# lid.net
KiCad netlist of a schematic drawn in EAGLE
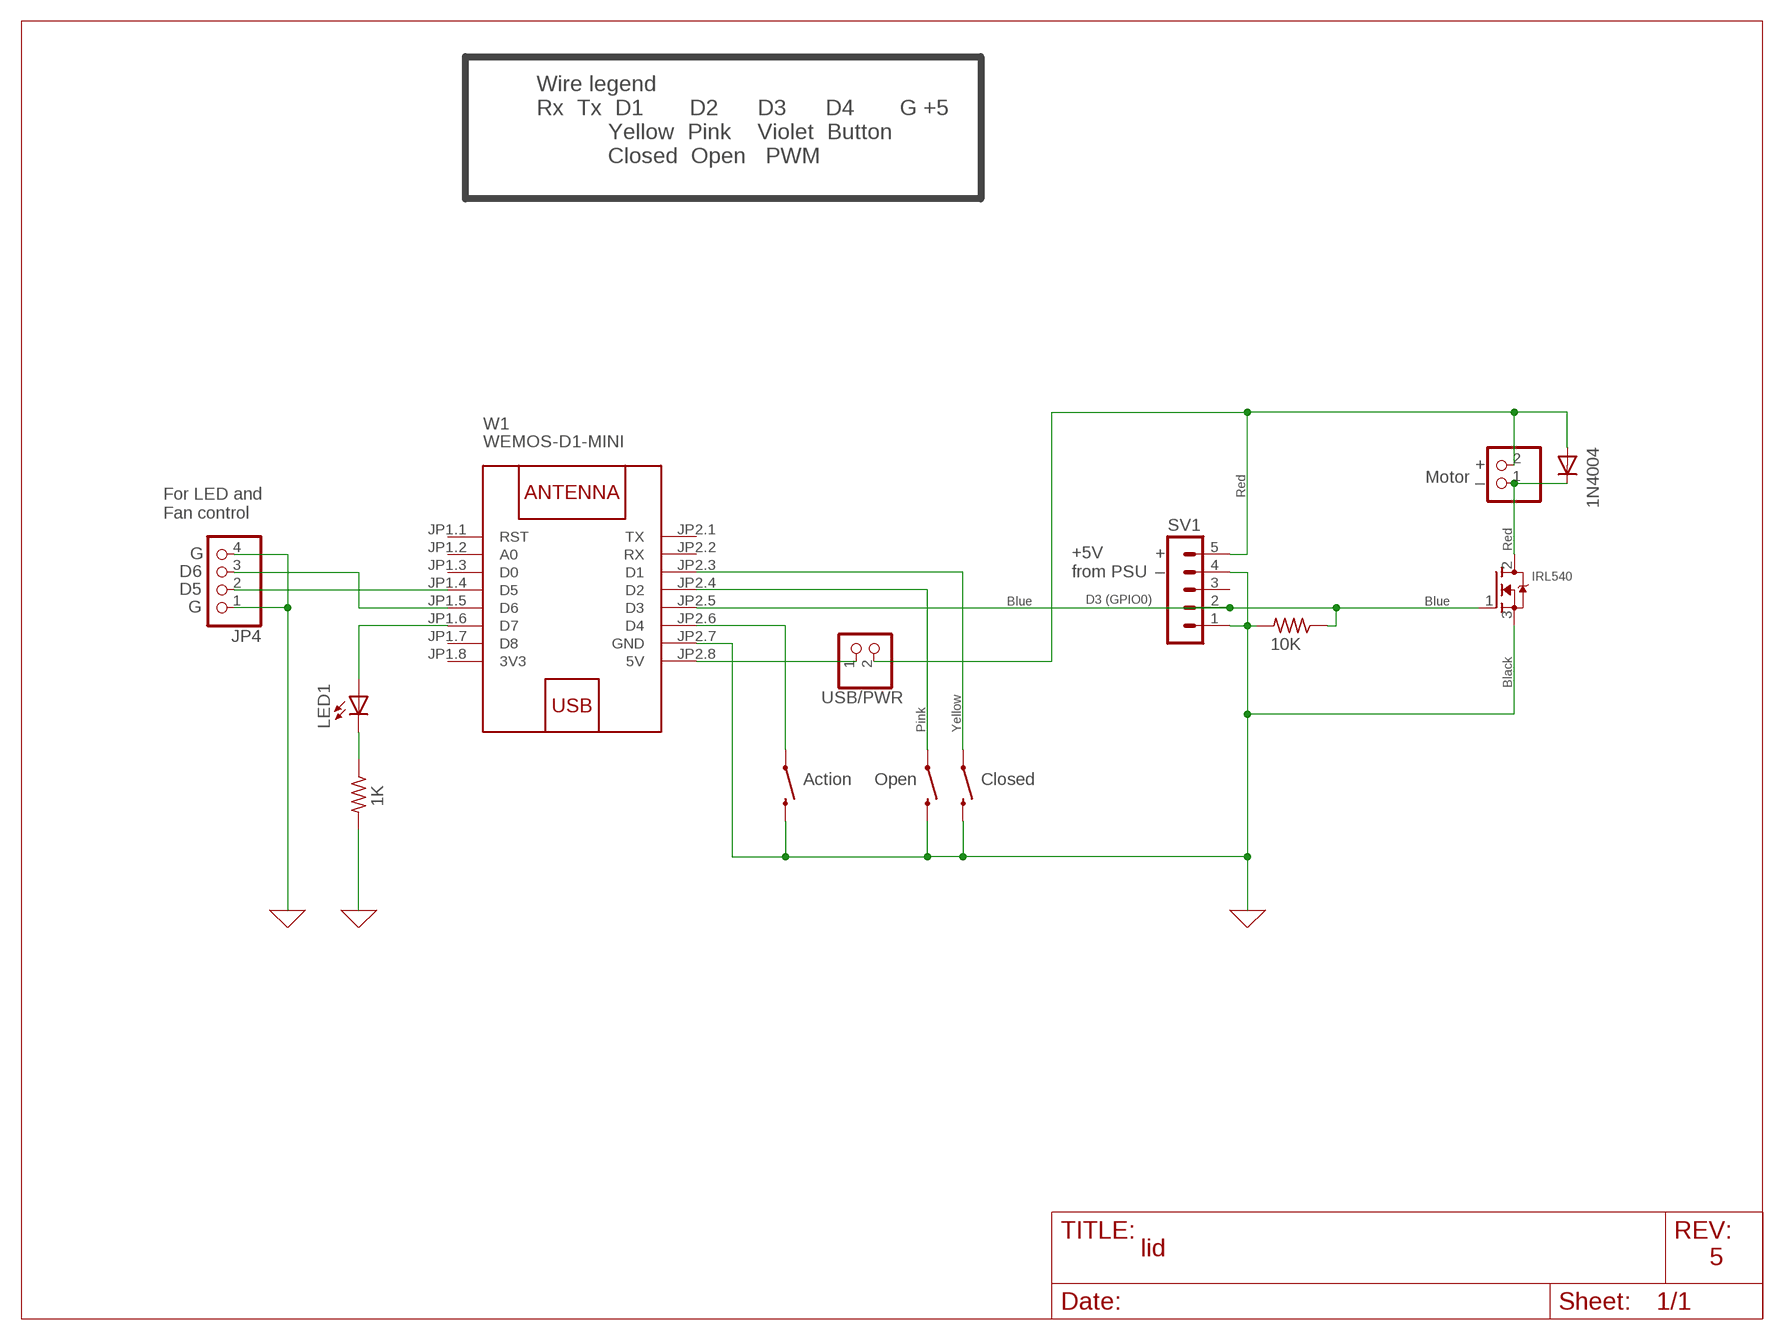
[diagram p0: schematic, sheet 1]

(export (version "E")
  (design (tool "Eeschema 10.0.6"))
  (components
    (comp (ref "ACTION")
      (value "MOMENTARY-SWITCH-SPST-PTH-6.0MM")
      (footprint "eagle-import:TACTILE_SWITCH_PTH_6.0MM")
      (libsource (lib "eagle-import") (part "MOMENTARY-SWITCH-SPST-PTH-6.0MM"))
    )
    (comp (ref "D1")
      (value "1N4004")
      (footprint "eagle-import:DO41-10")
      (libsource (lib "eagle-import") (part "1N4004"))
    )
    (comp (ref "JP3")
      (value "PINHD-1X2")
      (footprint "eagle-import:1X02")
      (libsource (lib "eagle-import") (part "PINHD-1X2"))
    )
    (comp (ref "JP4")
      (value "PINHD-1X4")
      (footprint "eagle-import:1X04")
      (libsource (lib "eagle-import") (part "PINHD-1X4"))
    )
    (comp (ref "LED1")
      (value "LED5MM")
      (footprint "eagle-import:LED5MM")
      (libsource (lib "eagle-import") (part "LED5MM"))
    )
    (comp (ref "Q1")
      (value "IRL540")
      (footprint "eagle-import:TO220V")
      (libsource (lib "eagle-import") (part "MOSFET-NGDS_TO220V"))
    )
    (comp (ref "R1")
      (value "1K")
      (footprint "eagle-import:0207_10")
      (libsource (lib "eagle-import") (part "R-US_0207/10"))
    )
    (comp (ref "R4")
      (value "10K")
      (footprint "eagle-import:0207_10")
      (libsource (lib "eagle-import") (part "R-US_0207/10"))
    )
    (comp (ref "S1")
      (value "MOMENTARY-SWITCH-SPST-PTH-6.0MM")
      (footprint "eagle-import:TACTILE_SWITCH_PTH_6.0MM")
      (libsource (lib "eagle-import") (part "MOMENTARY-SWITCH-SPST-PTH-6.0MM"))
    )
    (comp (ref "S2")
      (value "MOMENTARY-SWITCH-SPST-PTH-6.0MM")
      (footprint "eagle-import:TACTILE_SWITCH_PTH_6.0MM")
      (libsource (lib "eagle-import") (part "MOMENTARY-SWITCH-SPST-PTH-6.0MM"))
    )
    (comp (ref "SV1")
      (value "MA05-1")
      (footprint "eagle-import:MA05-1")
      (libsource (lib "eagle-import") (part "MA05-1"))
    )
    (comp (ref "USB/PWR")
      (value "PINHD-1X2")
      (footprint "eagle-import:1X02")
      (libsource (lib "eagle-import") (part "PINHD-1X2"))
    )
    (comp (ref "W1")
      (value "WEMOS-D1-MINI")
      (footprint "eagle-import:WEMOS-D1-MINI")
      (libsource (lib "eagle-import") (part "WEMOS-D1-MINI"))
    )
  )
  (nets
    (net (code "1") (name "/3V3") (class "Default")
      (node (ref "W1") (pin "JP1.8") (pinfunction "3V3_JP1.8") (pintype "power_in"))
    )
    (net (code "2") (name "GND") (class "Default")
      (node (ref "ACTION") (pin "3") (pinfunction "2_3") (pintype "passive"))
      (node (ref "JP4") (pin "1") (pinfunction "1_1") (pintype "passive"))
      (node (ref "JP4") (pin "4") (pinfunction "4_4") (pintype "passive"))
      (node (ref "Q1") (pin "3") (pinfunction "S_3") (pintype "bidirectional"))
      (node (ref "R1") (pin "2") (pinfunction "2_2") (pintype "passive"))
      (node (ref "R4") (pin "2") (pinfunction "2_2") (pintype "passive"))
      (node (ref "S1") (pin "3") (pinfunction "2_3") (pintype "passive"))
      (node (ref "S2") (pin "3") (pinfunction "2_3") (pintype "passive"))
      (node (ref "SV1") (pin "1") (pinfunction "1_1") (pintype "passive"))
      (node (ref "SV1") (pin "4") (pinfunction "4_4") (pintype "passive"))
      (node (ref "W1") (pin "JP2.7") (pinfunction "GND_JP2.7") (pintype "power_in"))
    )
    (net (code "3") (name "Net-(D1-PadA)") (class "Default")
      (node (ref "D1") (pin "A") (pinfunction "A_A") (pintype "passive"))
      (node (ref "JP3") (pin "2") (pinfunction "2_2") (pintype "passive"))
      (node (ref "SV1") (pin "5") (pinfunction "5_5") (pintype "passive"))
      (node (ref "USB/PWR") (pin "2") (pinfunction "2_2") (pintype "passive"))
    )
    (net (code "4") (name "Net-(LED1-C)") (class "Default")
      (node (ref "LED1") (pin "K") (pinfunction "C_K") (pintype "passive"))
      (node (ref "R1") (pin "1") (pinfunction "1_1") (pintype "passive"))
    )
    (net (code "5") (name "Net-(Q1-D)") (class "Default")
      (node (ref "D1") (pin "C") (pinfunction "C_C") (pintype "passive"))
      (node (ref "JP3") (pin "1") (pinfunction "1_1") (pintype "passive"))
      (node (ref "Q1") (pin "2") (pinfunction "D_2") (pintype "bidirectional"))
    )
    (net (code "6") (name "Net-(Q1-G)") (class "Default")
      (node (ref "Q1") (pin "1") (pinfunction "G_1") (pintype "bidirectional"))
      (node (ref "R4") (pin "1") (pinfunction "1_1") (pintype "passive"))
      (node (ref "SV1") (pin "2") (pinfunction "2_2") (pintype "passive"))
      (node (ref "W1") (pin "JP2.5") (pinfunction "D3_JP2.5") (pintype "bidirectional"))
    )
    (net (code "7") (name "Net-(W1-5V)") (class "Default")
      (node (ref "USB/PWR") (pin "1") (pinfunction "1_1") (pintype "passive"))
      (node (ref "W1") (pin "JP2.8") (pinfunction "5V_JP2.8") (pintype "power_in"))
    )
    (net (code "8") (name "Net-(W1-D1)") (class "Default")
      (node (ref "S2") (pin "1") (pinfunction "1_1") (pintype "passive"))
      (node (ref "W1") (pin "JP2.3") (pinfunction "D1_JP2.3") (pintype "bidirectional"))
    )
    (net (code "9") (name "Net-(W1-D2)") (class "Default")
      (node (ref "S1") (pin "1") (pinfunction "1_1") (pintype "passive"))
      (node (ref "W1") (pin "JP2.4") (pinfunction "D2_JP2.4") (pintype "bidirectional"))
    )
    (net (code "10") (name "Net-(W1-D4)") (class "Default")
      (node (ref "ACTION") (pin "1") (pinfunction "1_1") (pintype "passive"))
      (node (ref "W1") (pin "JP2.6") (pinfunction "D4_JP2.6") (pintype "bidirectional"))
    )
    (net (code "11") (name "Net-(W1-D5)") (class "Default")
      (node (ref "JP4") (pin "2") (pinfunction "2_2") (pintype "passive"))
      (node (ref "W1") (pin "JP1.4") (pinfunction "D5_JP1.4") (pintype "bidirectional"))
    )
    (net (code "12") (name "Net-(W1-D6)") (class "Default")
      (node (ref "JP4") (pin "3") (pinfunction "3_3") (pintype "passive"))
      (node (ref "W1") (pin "JP1.5") (pinfunction "D6_JP1.5") (pintype "bidirectional"))
    )
    (net (code "13") (name "Net-(W1-D7)") (class "Default")
      (node (ref "LED1") (pin "A") (pinfunction "A_A") (pintype "passive"))
      (node (ref "W1") (pin "JP1.6") (pinfunction "D7_JP1.6") (pintype "bidirectional"))
    )
    (net (code "14") (name "unconnected-(SV1-Pad3)") (class "Default")
      (node (ref "SV1") (pin "3") (pinfunction "3_3") (pintype "passive"))
    )
    (net (code "15") (name "unconnected-(W1-A0-PadJP1.2)") (class "Default")
      (node (ref "W1") (pin "JP1.2") (pinfunction "A0_JP1.2") (pintype "bidirectional"))
    )
    (net (code "16") (name "unconnected-(W1-D0-PadJP1.3)") (class "Default")
      (node (ref "W1") (pin "JP1.3") (pinfunction "D0_JP1.3") (pintype "bidirectional"))
    )
    (net (code "17") (name "unconnected-(W1-D8-PadJP1.7)") (class "Default")
      (node (ref "W1") (pin "JP1.7") (pinfunction "D8_JP1.7") (pintype "bidirectional"))
    )
    (net (code "18") (name "unconnected-(W1-RST-PadJP1.1)") (class "Default")
      (node (ref "W1") (pin "JP1.1") (pinfunction "RST_JP1.1") (pintype "bidirectional"))
    )
    (net (code "19") (name "unconnected-(W1-RX-PadJP2.2)") (class "Default")
      (node (ref "W1") (pin "JP2.2") (pinfunction "RX_JP2.2") (pintype "bidirectional"))
    )
    (net (code "20") (name "unconnected-(W1-TX-PadJP2.1)") (class "Default")
      (node (ref "W1") (pin "JP2.1") (pinfunction "TX_JP2.1") (pintype "bidirectional"))
    )
  )
)
